# Main.net
KiCad netlist of a schematic drawn in Altium Designer
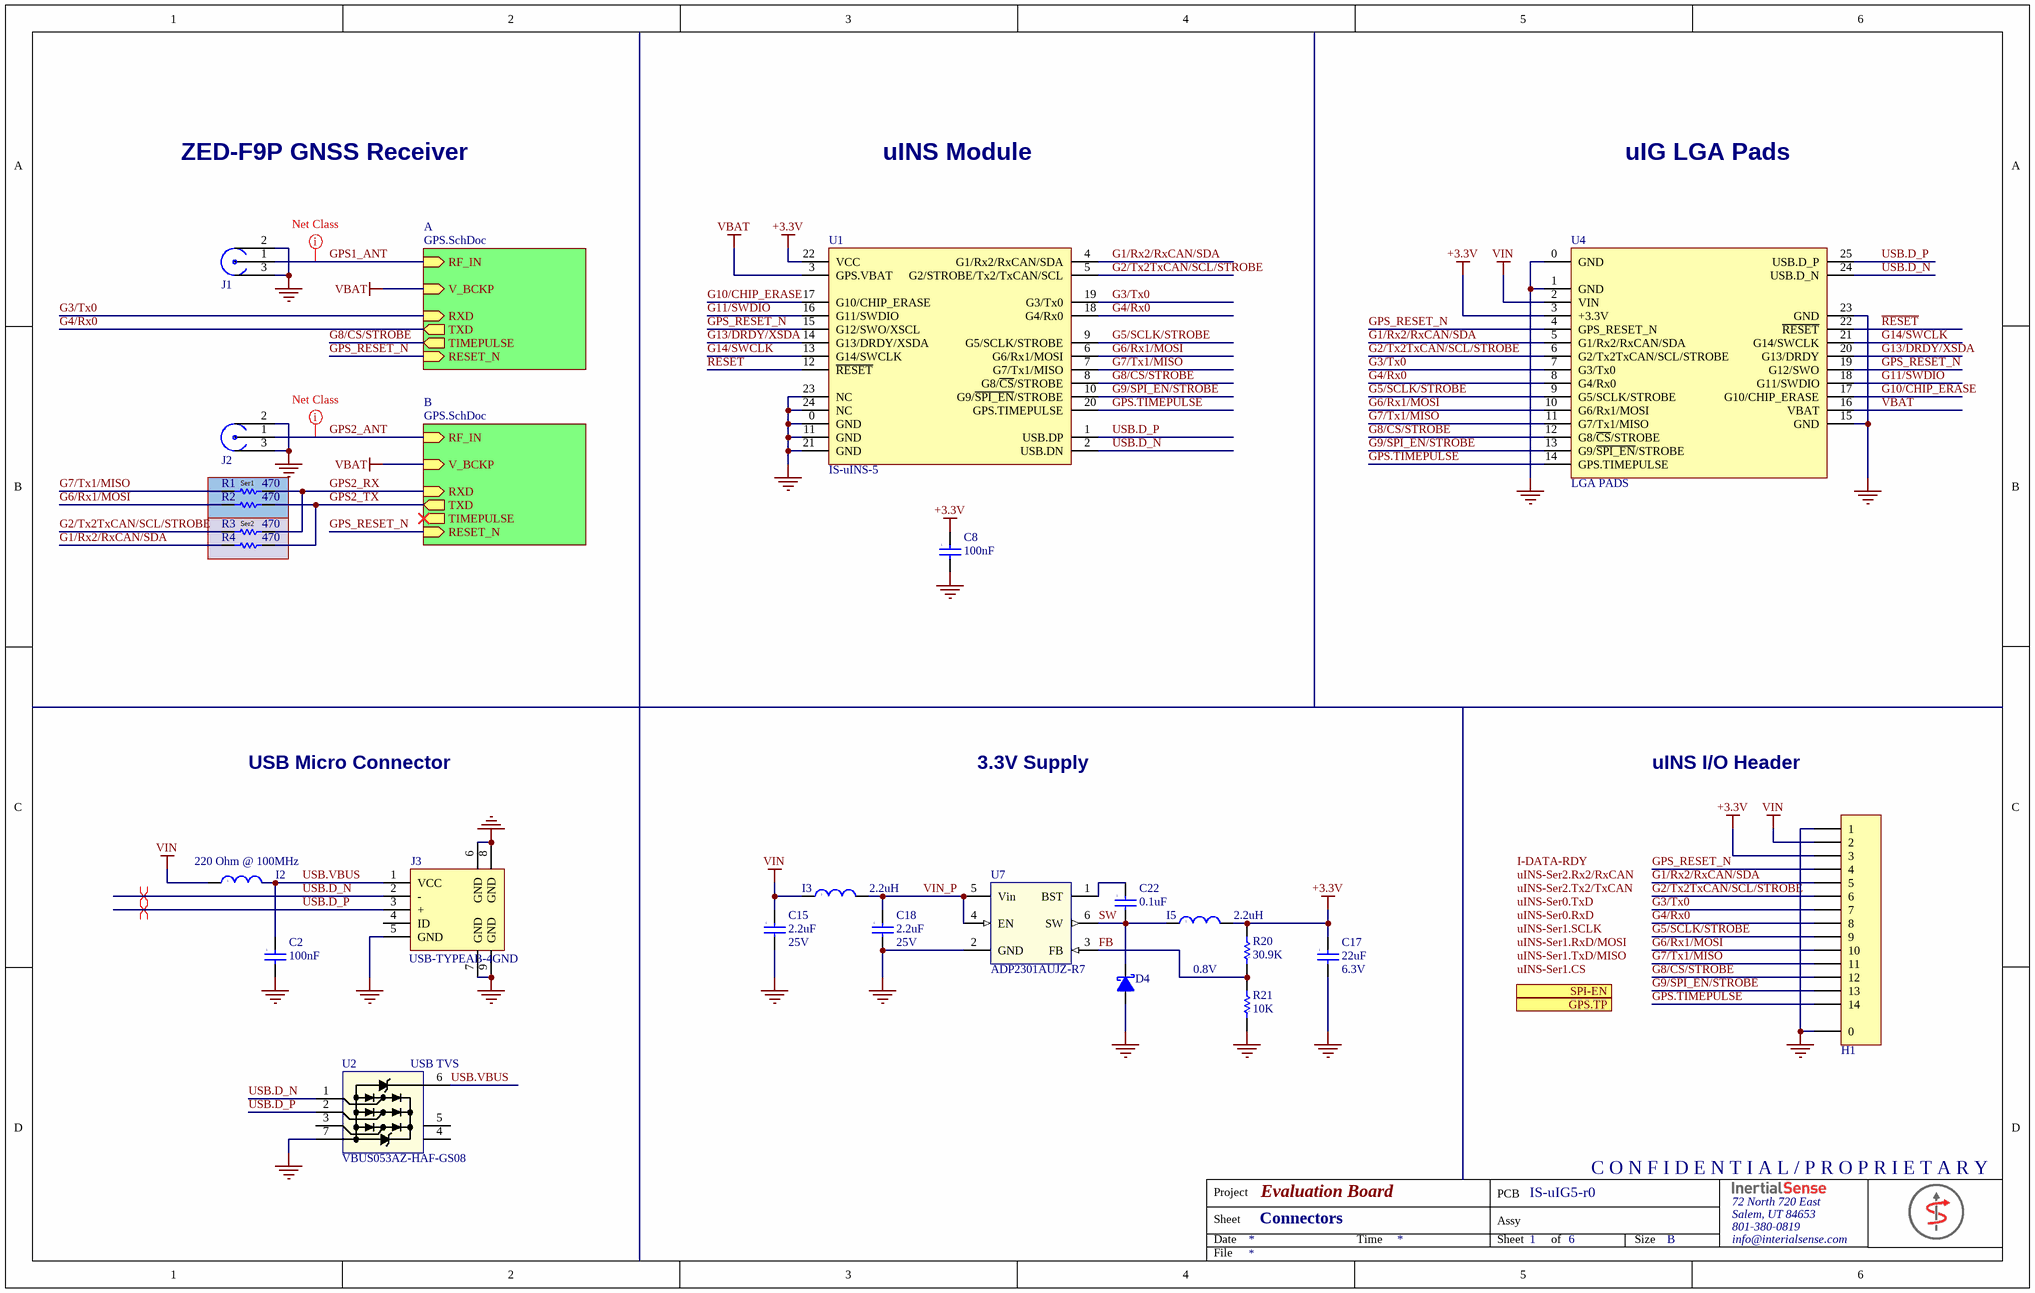
[diagram p0: Main.SchDoc]

(export (version "E")
  (design (tool "Eeschema 10.0.6"))
  (components
    (comp (ref "C2")
      (value "100nF")
      (footprint "0402")
      (description "CAP CER .10UF 50V X7R 10% 0402")
      (fields
        (field (name "MANUFACTURER") "TDK Corporation")
        (field (name "MANUFACTURER PART NUMBER") "C1005X7R1H104K")
        (field (name "PUBLISHER") "Altium Limited")
      )
      (libsource (lib "General") (part "Cap"))
    )
    (comp (ref "C8")
      (value "100nF")
      (footprint "0402")
      (description "CAP CER .10UF 50V X7R 10% 0402")
      (fields
        (field (name "MANUFACTURER") "TDK Corporation")
        (field (name "MANUFACTURER PART NUMBER") "C1005X7R1H104K")
        (field (name "PUBLISHER") "Altium Limited")
      )
      (libsource (lib "General") (part "Cap"))
    )
    (comp (ref "C15")
      (value "2.2uF")
      (footprint "0603")
      (description "CAP CER 2.2UF 25V X6S 0603")
      (fields
        (field (name "MANUFACTURER") "Murata")
        (field (name "MANUFACTURER PART NUMBER") "GRT188C81E225KE13D")
        (field (name "VOLTAGE RATING") "25V")
        (field (name "PUBLISHER") "Altium Limited")
      )
      (libsource (lib "") (part "Cap_1"))
    )
    (comp (ref "C17")
      (value "22uF")
      (footprint "0603")
      (description "CAP CER 22UF 6.3V X6S 0603")
      (fields
        (field (name "MANUFACTURER") "Murata")
        (field (name "MANUFACTURER PART NUMBER") "GRM188C80J226ME15D")
        (field (name "VOLTAGE RATING") "6.3V")
        (field (name "PUBLISHER") "Altium Limited")
      )
      (libsource (lib "") (part "Cap_1"))
    )
    (comp (ref "C18")
      (value "2.2uF")
      (footprint "0603")
      (description "CAP CER 2.2UF 25V X6S 0603")
      (fields
        (field (name "MANUFACTURER") "Murata")
        (field (name "MANUFACTURER PART NUMBER") "GRT188C81E225KE13D")
        (field (name "VOLTAGE RATING") "25V")
        (field (name "PUBLISHER") "Altium Limited")
      )
      (libsource (lib "") (part "Cap_1"))
    )
    (comp (ref "C22")
      (value "0.1uF")
      (footprint "0402")
      (description "CAP CER 0.1UF 50V X7R 0402")
      (fields
        (field (name "MANUFACTURER") "TDK")
        (field (name "MANUFACTURER PART NUMBER") "CGA2B3X7R1H104K050BB")
        (field (name "PUBLISHER") "Altium Limited")
      )
      (libsource (lib "") (part "Cap_1"))
    )
    (comp (ref "D4")
      (value "Diode - Schottky")
      (footprint "D0603B")
      (description "DIODE SCHOTTKY 30V 2A 0603")
      (fields
        (field (name "MANUFACTURER") "Vishay")
        (field (name "MANUFACTURER PART NUMBER") "VSKY20301608-G4-08")
      )
      (libsource (lib "General") (part "Diode - Schottky"))
    )
    (comp (ref "H1")
      (value "Hdr - 14pin - mount")
      (footprint "SM14B-GHS-TB(LF)(SN)")
      (description "Conn Shrouded Header HDR 14 POS 1.25mm Solder ST Top Entry SMD T/R")
      (fields
        (field (name "MANUFACTURER") "JST")
        (field (name "MANUFACTURER PART NUMBER") "SM14B-GHS-TB(LF)(SN)")
      )
      (libsource (lib "Connectors") (part "Hdr - 14pin - mount"))
    )
    (comp (ref "I2")
      (value "220 Ohm @ 100MHz")
      (footprint "I0603")
      (description "FERRITE CHIP 220 OHM 2500MA 0603")
      (fields
        (field (name "MANUFACTURER") "Murata Electronics North America")
        (field (name "MANUFACTURER PART NUMBER") "BLM18SG221TN1D")
      )
      (libsource (lib "") (part "Inductor_1"))
    )
    (comp (ref "I3")
      (value "2.2uH")
      (footprint "0806")
      (description "FIXED IND 2.2UH 1.2A 110 MOHM")
      (fields
        (field (name "MANUFACTURER") "TDK")
        (field (name "MANUFACTURER PART NUMBER") "MLP2016H2R2MT0S1")
      )
      (libsource (lib "General") (part "Inductor"))
    )
    (comp (ref "I5")
      (value "2.2uH")
      (footprint "0806")
      (description "FIXED IND 2.2UH 1.2A 110 MOHM")
      (fields
        (field (name "MANUFACTURER") "TDK")
        (field (name "MANUFACTURER PART NUMBER") "MLP2016H2R2MT0S1")
      )
      (libsource (lib "General") (part "Inductor"))
    )
    (comp (ref "J1")
      (value "RF - GND x 2")
      (footprint "RF UMC SMD")
      (description "CONN UMC RCPT STR 50 OHM SMD")
      (fields
        (field (name "MANUFACTURER") "Emerson Network Power Connectivity Johnson")
        (field (name "MANUFACTURER PART NUMBER") "128-0711-201")
      )
      (libsource (lib "Connectors") (part "RF - GND x 2"))
    )
    (comp (ref "J2")
      (value "RF - GND x 2")
      (footprint "RF UMC SMD")
      (description "CONN UMC RCPT STR 50 OHM SMD")
      (fields
        (field (name "MANUFACTURER") "Emerson Network Power Connectivity Johnson")
        (field (name "MANUFACTURER PART NUMBER") "128-0711-201")
      )
      (libsource (lib "Connectors") (part "RF - GND x 2"))
    )
    (comp (ref "J3")
      (value "USB-TYPEAB-4GND")
      (footprint "USB Micro AB R/A THR")
      (description "CONN USB AB 4POS")
      (fields
        (field (name "MANUFACTURER") "Amphenol FCI")
        (field (name "MANUFACTURER PART NUMBER") "10118194-0001LF")
      )
      (libsource (lib "Connectors") (part "USB-TYPEAB-4GND"))
    )
    (comp (ref "R1")
      (value "470")
      (footprint "R0402")
      (description "RES 470 OHM 1/16W 1% 0402 SMD")
      (fields
        (field (name "MANUFACTURER") "Vishay Dale")
        (field (name "MANUFACTURER PART NUMBER") "CRCW0402470RFKED")
      )
      (libsource (lib "") (part "Res_1"))
    )
    (comp (ref "R2")
      (value "470")
      (footprint "R0402")
      (description "RES 470 OHM 1/16W 1% 0402 SMD")
      (fields
        (field (name "MANUFACTURER") "Vishay Dale")
        (field (name "MANUFACTURER PART NUMBER") "CRCW0402470RFKED")
      )
      (libsource (lib "") (part "Res_1"))
    )
    (comp (ref "R3")
      (value "470")
      (footprint "R0402")
      (description "RES 470 OHM 1/16W 1% 0402 SMD")
      (fields
        (field (name "MANUFACTURER") "Vishay Dale")
        (field (name "MANUFACTURER PART NUMBER") "CRCW0402470RFKED")
      )
      (libsource (lib "") (part "Res_1"))
    )
    (comp (ref "R4")
      (value "470")
      (footprint "R0402")
      (description "RES 470 OHM 1/16W 1% 0402 SMD")
      (fields
        (field (name "MANUFACTURER") "Vishay Dale")
        (field (name "MANUFACTURER PART NUMBER") "CRCW0402470RFKED")
      )
      (libsource (lib "") (part "Res_1"))
    )
    (comp (ref "R20")
      (value "30.9K")
      (footprint "R0402")
      (description "RES TF 30.9K OHM 1% 1/16W 0402")
      (fields
        (field (name "MANUFACTURER") "Stackpole Electronics Inc")
        (field (name "MANUFACTURER PART NUMBER") "RMCF0402FT30K9")
      )
      (libsource (lib "General") (part "Res"))
    )
    (comp (ref "R21")
      (value "10K")
      (footprint "R0402")
      (description "RES 10.0K OHM 1/16W 1% 0402 SMD")
      (fields
        (field (name "MANUFACTURER") "Yageo")
        (field (name "MANUFACTURER PART NUMBER") "RC0402FR-0710KL")
      )
      (libsource (lib "General") (part "Res"))
    )
    (comp (ref "U1")
      (value "uINS")
      (footprint "IS-uINS-5.0")
      (description "Inertial Sense uINS")
      (fields
        (field (name "MANUFACTURER") "Inertial Sense")
        (field (name "MANUFACTURER PART NUMBER") "IS-uINS-5")
      )
      (libsource (lib "IS-uINS-5") (part "IS-uINS-5.0"))
    )
    (comp (ref "U2")
      (value "VBUS053")
      (footprint "QFN50P160X160X60-6N")
      (description "ESD SUPPRESS 5.5V 36W 3-Line USB")
      (fields
        (field (name "MANUFACTURER") "Vishay Semiconductors")
        (field (name "MANUFACTURER PART NUMBER") "VBUS053AZ-HAF-GS08")
      )
      (libsource (lib "ICs") (part "VBUS053"))
    )
    (comp (ref "U4")
      (value "LGA PADS")
      (footprint "uIG-1.0_LGA")
      (description "Inertial Sense uIG5 GNSS INS Module")
      (libsource (lib "Sensors") (part "uIG1p0_LGA"))
    )
    (comp (ref "U7")
      (value "ADP2301")
      (footprint "MO-178-AB")
      (description "IC BUCK ADJ 1.2A 6TSOT")
      (fields
        (field (name "MANUFACTURER") "Analog Devices Inc")
        (field (name "MANUFACTURER PART NUMBER") "ADP2301AUJZ-R7")
      )
      (libsource (lib "ICs") (part "ADP2301"))
    )
  )
  (nets
    (net (code "1") (name "+3.3V") (class "Default")
      (node (ref "C17") (pin "1") (pinfunction "1_1") (pintype "passive"))
      (node (ref "C8") (pin "1") (pinfunction "1_1") (pintype "passive"))
      (node (ref "H1") (pin "3") (pinfunction "3_3") (pintype "passive"))
      (node (ref "I5") (pin "2") (pinfunction "2_2") (pintype "passive"))
      (node (ref "R20") (pin "2") (pinfunction "2_2") (pintype "passive"))
      (node (ref "U1") (pin "22") (pinfunction "VCC_22") (pintype "power_in"))
      (node (ref "U4") (pin "3") (pinfunction "+3.3V_3") (pintype "passive"))
    )
    (net (code "2") (name "/FB") (class "Default")
      (node (ref "R20") (pin "1") (pinfunction "1_1") (pintype "passive"))
      (node (ref "R21") (pin "2") (pinfunction "2_2") (pintype "passive"))
      (node (ref "U7") (pin "3") (pinfunction "FB_3") (pintype "input"))
    )
    (net (code "3") (name "/G1{slash}Rx2{slash}RxCAN{slash}SDA") (class "Default")
      (node (ref "H1") (pin "5") (pinfunction "5_5") (pintype "passive"))
      (node (ref "R4") (pin "1") (pinfunction "1_1") (pintype "passive"))
      (node (ref "U1") (pin "4") (pinfunction "G1/Rx2/RxCAN/SDA_4") (pintype "passive"))
      (node (ref "U4") (pin "5") (pinfunction "G1/Rx2/RxCAN/SDA_5") (pintype "passive"))
    )
    (net (code "4") (name "/G2{slash}Tx2TxCAN{slash}SCL{slash}STROBE") (class "Default")
      (node (ref "H1") (pin "6") (pinfunction "6_6") (pintype "passive"))
      (node (ref "R3") (pin "1") (pinfunction "1_1") (pintype "passive"))
      (node (ref "U1") (pin "5") (pinfunction "G2/STROBE/Tx2/TxCAN/SCL_5") (pintype "passive"))
      (node (ref "U4") (pin "6") (pinfunction "G2/Tx2TxCAN/SCL/STROBE_6") (pintype "passive"))
    )
    (net (code "5") (name "/G3{slash}Tx0") (class "Default")
      (node (ref "H1") (pin "7") (pinfunction "7_7") (pintype "passive"))
      (node (ref "U1") (pin "19") (pinfunction "G3/Tx0_19") (pintype "passive"))
      (node (ref "U4") (pin "7") (pinfunction "G3/Tx0_7") (pintype "passive"))
    )
    (net (code "6") (name "/G4{slash}Rx0") (class "Default")
      (node (ref "H1") (pin "8") (pinfunction "8_8") (pintype "passive"))
      (node (ref "U1") (pin "18") (pinfunction "G4/Rx0_18") (pintype "passive"))
      (node (ref "U4") (pin "8") (pinfunction "G4/Rx0_8") (pintype "passive"))
    )
    (net (code "7") (name "/G5{slash}SCLK{slash}STROBE") (class "Default")
      (node (ref "H1") (pin "9") (pinfunction "9_9") (pintype "passive"))
      (node (ref "U1") (pin "9") (pinfunction "G5/SCLK/STROBE_9") (pintype "passive"))
      (node (ref "U4") (pin "9") (pinfunction "G5/SCLK/STROBE_9") (pintype "passive"))
    )
    (net (code "8") (name "/G6{slash}Rx1{slash}MOSI") (class "Default")
      (node (ref "H1") (pin "10") (pinfunction "10_10") (pintype "passive"))
      (node (ref "R2") (pin "1") (pinfunction "1_1") (pintype "passive"))
      (node (ref "U1") (pin "6") (pinfunction "G6/Rx1/MOSI_6") (pintype "passive"))
      (node (ref "U4") (pin "10") (pinfunction "G6/Rx1/MOSI_10") (pintype "passive"))
    )
    (net (code "9") (name "/G7{slash}Tx1{slash}MISO") (class "Default")
      (node (ref "H1") (pin "11") (pinfunction "11_11") (pintype "passive"))
      (node (ref "R1") (pin "1") (pinfunction "1_1") (pintype "passive"))
      (node (ref "U1") (pin "7") (pinfunction "G7/Tx1/MISO_7") (pintype "passive"))
      (node (ref "U4") (pin "11") (pinfunction "G7/Tx1/MISO_11") (pintype "passive"))
    )
    (net (code "10") (name "/G8{slash}~{CS}{slash}STROBE") (class "Default")
      (node (ref "H1") (pin "12") (pinfunction "12_12") (pintype "passive"))
      (node (ref "U1") (pin "8") (pinfunction "G8/~{CS}/STROBE_8") (pintype "passive"))
      (node (ref "U4") (pin "12") (pinfunction "G8/~{CS}/STROBE_12") (pintype "passive"))
    )
    (net (code "11") (name "/G9{slash}~{SPI_EN}{slash}STROBE") (class "Default")
      (node (ref "H1") (pin "13") (pinfunction "13_13") (pintype "passive"))
      (node (ref "U1") (pin "10") (pinfunction "G9/~{SPI_EN}/STROBE_10") (pintype "passive"))
      (node (ref "U4") (pin "13") (pinfunction "G9/~{SPI_EN}/STROBE_13") (pintype "passive"))
    )
    (net (code "12") (name "/G10{slash}CHIP_ERASE") (class "Default")
      (node (ref "U1") (pin "17") (pinfunction "G10/CHIP_ERASE_17") (pintype "passive"))
      (node (ref "U4") (pin "17") (pinfunction "G10/CHIP_ERASE_17") (pintype "passive"))
    )
    (net (code "13") (name "/G11{slash}SWDIO") (class "Default")
      (node (ref "U1") (pin "16") (pinfunction "G11/SWDIO_16") (pintype "passive"))
      (node (ref "U4") (pin "18") (pinfunction "G11/SWDIO_18") (pintype "passive"))
    )
    (net (code "14") (name "/G13{slash}DRDY{slash}XSDA") (class "Default")
      (node (ref "U1") (pin "14") (pinfunction "G13/DRDY/XSDA_14") (pintype "passive"))
      (node (ref "U4") (pin "20") (pinfunction "G13/DRDY_20") (pintype "passive"))
    )
    (net (code "15") (name "/G14{slash}SWCLK") (class "Default")
      (node (ref "U1") (pin "13") (pinfunction "G14/SWCLK_13") (pintype "passive"))
      (node (ref "U4") (pin "21") (pinfunction "G14/SWCLK_21") (pintype "passive"))
    )
    (net (code "16") (name "/GPS.TIMEPULSE") (class "Default")
      (node (ref "H1") (pin "14") (pinfunction "14_14") (pintype "passive"))
      (node (ref "U1") (pin "20") (pinfunction "GPS.TIMEPULSE_20") (pintype "passive"))
      (node (ref "U4") (pin "14") (pinfunction "GPS.TIMEPULSE_14") (pintype "passive"))
    )
    (net (code "18") (name "/GPS1_ANT") (class "Default")
      (node (ref "J1") (pin "1") (pinfunction "1_1") (pintype "passive"))
    )
    (net (code "19") (name "/GPS2_ANT") (class "Default")
      (node (ref "J2") (pin "1") (pinfunction "1_1") (pintype "passive"))
    )
    (net (code "20") (name "/GPS2_RX") (class "Default")
      (node (ref "R1") (pin "2") (pinfunction "2_2") (pintype "passive"))
      (node (ref "R3") (pin "2") (pinfunction "2_2") (pintype "passive"))
    )
    (net (code "21") (name "/GPS2_TX") (class "Default")
      (node (ref "R2") (pin "2") (pinfunction "2_2") (pintype "passive"))
      (node (ref "R4") (pin "2") (pinfunction "2_2") (pintype "passive"))
    )
    (net (code "22") (name "/GPS_RESET_N") (class "Default")
      (node (ref "H1") (pin "4") (pinfunction "4_4") (pintype "passive"))
      (node (ref "U1") (pin "15") (pinfunction "G12/SWO/XSCL_15") (pintype "passive"))
      (node (ref "U4") (pin "19") (pinfunction "G12/SWO_19") (pintype "passive"))
      (node (ref "U4") (pin "4") (pinfunction "GPS_RESET_N_4") (pintype "passive"))
    )
    (net (code "24") (name "/RESET") (class "Default")
      (node (ref "U1") (pin "12") (pinfunction "~{RESET}_12") (pintype "passive"))
      (node (ref "U4") (pin "22") (pinfunction "~{RESET}_22") (pintype "passive"))
    )
    (net (code "26") (name "/SW") (class "Default")
      (node (ref "C22") (pin "2") (pinfunction "2_2") (pintype "passive"))
      (node (ref "D4") (pin "C") (pinfunction "C_C") (pintype "passive"))
      (node (ref "I5") (pin "1") (pinfunction "1_1") (pintype "passive"))
      (node (ref "U7") (pin "6") (pinfunction "SW_6") (pintype "output"))
    )
    (net (code "28") (name "/USB.D_N") (class "Default")
      (node (ref "J3") (pin "2") (pinfunction "-_2") (pintype "passive"))
      (node (ref "U1") (pin "2") (pinfunction "USB.DN_2") (pintype "passive"))
      (node (ref "U2") (pin "1") (pintype "passive"))
      (node (ref "U4") (pin "24") (pinfunction "USB.D_N_24") (pintype "passive"))
    )
    (net (code "29") (name "/USB.D_P") (class "Default")
      (node (ref "J3") (pin "3") (pinfunction "+_3") (pintype "passive"))
      (node (ref "U1") (pin "1") (pinfunction "USB.DP_1") (pintype "passive"))
      (node (ref "U2") (pin "2") (pintype "passive"))
      (node (ref "U4") (pin "25") (pinfunction "USB.D_P_25") (pintype "passive"))
    )
    (net (code "30") (name "/USB.VBUS") (class "Default")
      (node (ref "C2") (pin "1") (pinfunction "1_1") (pintype "passive"))
      (node (ref "I2") (pin "2") (pinfunction "2_2") (pintype "passive"))
      (node (ref "J3") (pin "1") (pinfunction "VCC_1") (pintype "passive"))
      (node (ref "U2") (pin "6") (pintype "passive"))
    )
    (net (code "31") (name "/VIN_P") (class "Default")
      (node (ref "C18") (pin "1") (pinfunction "1_1") (pintype "passive"))
      (node (ref "I3") (pin "2") (pinfunction "2_2") (pintype "passive"))
      (node (ref "U7") (pin "4") (pinfunction "EN_4") (pintype "input"))
      (node (ref "U7") (pin "5") (pinfunction "Vin_5") (pintype "power_in"))
    )
    (net (code "40") (name "GND") (class "Default")
      (node (ref "C15") (pin "2") (pinfunction "2_2") (pintype "passive"))
      (node (ref "C17") (pin "2") (pinfunction "2_2") (pintype "passive"))
      (node (ref "C18") (pin "2") (pinfunction "2_2") (pintype "passive"))
      (node (ref "C2") (pin "2") (pinfunction "2_2") (pintype "passive"))
      (node (ref "C8") (pin "2") (pinfunction "2_2") (pintype "passive"))
      (node (ref "D4") (pin "A") (pinfunction "A_A") (pintype "passive"))
      (node (ref "H1") (pin "0") (pinfunction "0_0") (pintype "passive"))
      (node (ref "H1") (pin "1") (pinfunction "1_1") (pintype "passive"))
      (node (ref "J1") (pin "2") (pinfunction "2_2") (pintype "passive"))
      (node (ref "J1") (pin "3") (pinfunction "3_3") (pintype "passive"))
      (node (ref "J2") (pin "2") (pinfunction "2_2") (pintype "passive"))
      (node (ref "J2") (pin "3") (pinfunction "3_3") (pintype "passive"))
      (node (ref "J3") (pin "5") (pinfunction "GND_5") (pintype "passive"))
      (node (ref "J3") (pin "6") (pinfunction "GND_6") (pintype "passive"))
      (node (ref "J3") (pin "7") (pinfunction "GND_7") (pintype "passive"))
      (node (ref "J3") (pin "8") (pinfunction "GND_8") (pintype "passive"))
      (node (ref "J3") (pin "9") (pinfunction "GND_9") (pintype "passive"))
      (node (ref "R21") (pin "1") (pinfunction "1_1") (pintype "passive"))
      (node (ref "U1") (pin "0") (pinfunction "GND_0") (pintype "power_in"))
      (node (ref "U1") (pin "11") (pinfunction "GND_11") (pintype "power_in"))
      (node (ref "U1") (pin "21") (pinfunction "GND_21") (pintype "power_in"))
      (node (ref "U1") (pin "23") (pinfunction "NC_23") (pintype "power_in"))
      (node (ref "U1") (pin "24") (pinfunction "NC_24") (pintype "power_in"))
      (node (ref "U2") (pin "7") (pintype "passive"))
      (node (ref "U4") (pin "0") (pinfunction "GND_0") (pintype "passive"))
      (node (ref "U4") (pin "1") (pinfunction "GND_1") (pintype "passive"))
      (node (ref "U4") (pin "15") (pinfunction "GND_15") (pintype "passive"))
      (node (ref "U4") (pin "23") (pinfunction "GND_23") (pintype "passive"))
      (node (ref "U7") (pin "2") (pinfunction "GND_2") (pintype "power_in"))
    )
    (net (code "41") (name "Net-(U7-BST)") (class "Default")
      (node (ref "C22") (pin "1") (pinfunction "1_1") (pintype "passive"))
      (node (ref "U7") (pin "1") (pinfunction "BST_1") (pintype "passive"))
    )
    (net (code "42") (name "VBAT") (class "Default")
      (node (ref "U1") (pin "3") (pinfunction "GPS.VBAT_3") (pintype "passive"))
      (node (ref "U4") (pin "16") (pinfunction "VBAT_16") (pintype "passive"))
    )
    (net (code "43") (name "VIN") (class "Default")
      (node (ref "C15") (pin "1") (pinfunction "1_1") (pintype "passive"))
      (node (ref "H1") (pin "2") (pinfunction "2_2") (pintype "passive"))
      (node (ref "I2") (pin "1") (pinfunction "1_1") (pintype "passive"))
      (node (ref "I3") (pin "1") (pinfunction "1_1") (pintype "passive"))
      (node (ref "U4") (pin "2") (pinfunction "VIN_2") (pintype "passive"))
    )
    (net (code "44") (name "unconnected-(J3-ID-Pad4)") (class "Default")
      (node (ref "J3") (pin "4") (pinfunction "ID_4") (pintype "passive"))
    )
    (net (code "45") (name "unconnected-(U2-Pad3)") (class "Default")
      (node (ref "U2") (pin "3") (pintype "passive"))
    )
    (net (code "46") (name "unconnected-(U2-nc-Pad4)") (class "Default")
      (node (ref "U2") (pin "4") (pinfunction "nc_4") (pintype "passive"))
    )
    (net (code "47") (name "unconnected-(U2-nc-Pad5)") (class "Default")
      (node (ref "U2") (pin "5") (pinfunction "nc_5") (pintype "passive"))
    )
  )
)
